# SD.net
KiCad netlist of a schematic drawn in Altium Designer
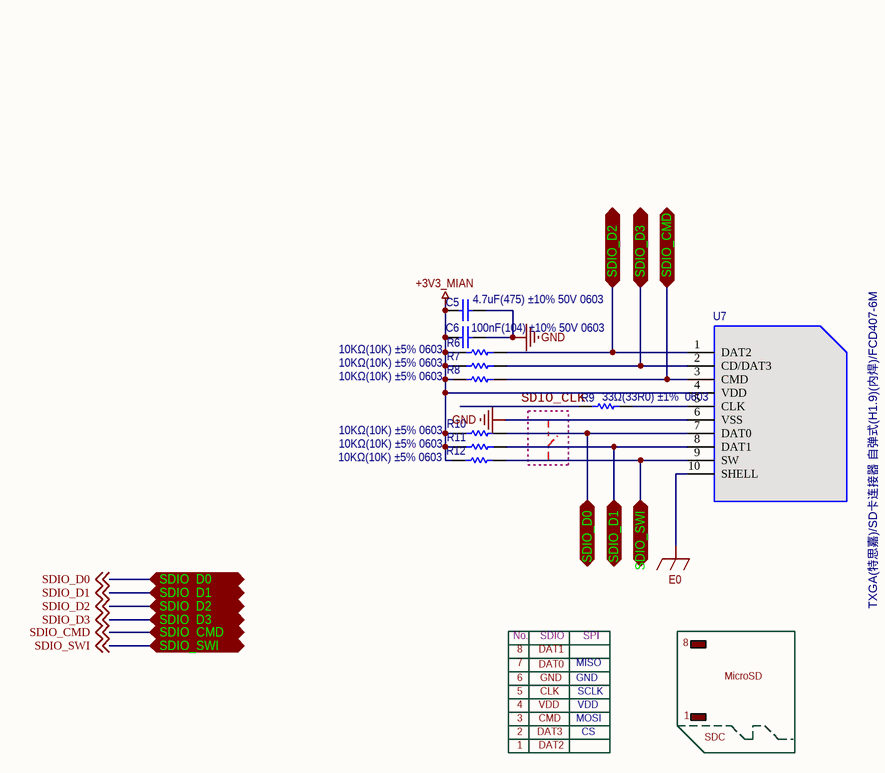
[diagram p0: SD.SchDoc]

(export (version "E")
  (design (tool "Eeschema 10.0.6"))
  (components
    (comp (ref "C5")
      (value "4.7uF(475) ±10% 50V 0603")
      (footprint "C0603")
      (description "Capacitor")
      (fields (field (name "PUBLISHER") "Altium Limited"))
      (libsource (lib "Miscellaneous Devices") (part "Cap"))
    )
    (comp (ref "C6")
      (value "100nF(104) ±10% 50V 0603")
      (footprint "C0603")
      (description "Capacitor")
      (fields (field (name "PUBLISHER") "Altium Limited"))
      (libsource (lib "Miscellaneous Devices") (part "Cap"))
    )
    (comp (ref "R6")
      (value "10KΩ(10K) ±5% 0603")
      (footprint "R0603")
      (description "Resistor")
      (fields (field (name "PUBLISHER") "Altium Limited"))
      (libsource (lib "Miscellaneous Devices") (part "Res1"))
    )
    (comp (ref "R7")
      (value "10KΩ(10K) ±5% 0603")
      (footprint "R0603")
      (description "Resistor")
      (fields (field (name "PUBLISHER") "Altium Limited"))
      (libsource (lib "Miscellaneous Devices") (part "Res1"))
    )
    (comp (ref "R8")
      (value "10KΩ(10K) ±5% 0603")
      (footprint "R0603")
      (description "Resistor")
      (fields (field (name "PUBLISHER") "Altium Limited"))
      (libsource (lib "Miscellaneous Devices") (part "Res1"))
    )
    (comp (ref "R9")
      (value "33Ω(33R0) ±1%  0603")
      (footprint "R0603")
      (description "Resistor")
      (fields (field (name "PUBLISHER") "Altium Limited"))
      (libsource (lib "Miscellaneous Devices") (part "Res1"))
    )
    (comp (ref "R10")
      (value "10KΩ(10K) ±5% 0603")
      (footprint "R0603")
      (description "Resistor")
      (fields (field (name "PUBLISHER") "Altium Limited"))
      (libsource (lib "Miscellaneous Devices") (part "Res1"))
    )
    (comp (ref "R11")
      (value "10KΩ(10K) ±5% 0603")
      (footprint "R0603")
      (description "Resistor")
      (fields (field (name "PUBLISHER") "Altium Limited"))
      (libsource (lib "Miscellaneous Devices") (part "Res1"))
    )
    (comp (ref "R12")
      (value "10KΩ(10K) ±5% 0603")
      (footprint "R0603")
      (description "Resistor")
      (fields (field (name "PUBLISHER") "Altium Limited"))
      (libsource (lib "Miscellaneous Devices") (part "Res1"))
    )
    (comp (ref "U7")
      (value "TXGA(特思嘉)/SD卡连接器 自弹式(H1.9)(内焊)/FCD407-6M")
      (footprint "Micro SD")
      (libsource (lib "Tek") (part "SD CARD/FCD407-6M"))
    )
  )
  (nets
    (net (code "1") (name "+3V3_MIAN") (class "Default")
      (node (ref "C5") (pin "1") (pinfunction "1_1") (pintype "passive"))
      (node (ref "C6") (pin "2") (pinfunction "2_2") (pintype "passive"))
      (node (ref "R10") (pin "2") (pinfunction "2_2") (pintype "passive"))
      (node (ref "R11") (pin "2") (pinfunction "2_2") (pintype "passive"))
      (node (ref "R12") (pin "2") (pinfunction "2_2") (pintype "passive"))
      (node (ref "R6") (pin "2") (pinfunction "2_2") (pintype "passive"))
      (node (ref "R7") (pin "2") (pinfunction "2_2") (pintype "passive"))
      (node (ref "R8") (pin "2") (pinfunction "2_2") (pintype "passive"))
      (node (ref "U7") (pin "4") (pinfunction "VDD_4") (pintype "passive"))
    )
    (net (code "2") (name "/SDIO_CLK") (class "Default")
      (node (ref "R9") (pin "2") (pinfunction "2_2") (pintype "passive"))
    )
    (net (code "3") (name "E0") (class "Default")
      (node (ref "U7") (pin "10") (pinfunction "SHELL_10") (pintype "passive"))
    )
    (net (code "4") (name "GND") (class "Default")
      (node (ref "C5") (pin "2") (pinfunction "2_2") (pintype "passive"))
      (node (ref "C6") (pin "1") (pinfunction "1_1") (pintype "passive"))
      (node (ref "U7") (pin "6") (pinfunction "VSS_6") (pintype "passive"))
    )
    (net (code "5") (name "Net-(U7-CLK)") (class "Default")
      (node (ref "R9") (pin "1") (pinfunction "1_1") (pintype "passive"))
      (node (ref "U7") (pin "5") (pinfunction "CLK_5") (pintype "passive"))
    )
    (net (code "6") (name "SDIO_CMD") (class "Default")
      (node (ref "R8") (pin "1") (pinfunction "1_1") (pintype "passive"))
      (node (ref "U7") (pin "3") (pinfunction "CMD_3") (pintype "passive"))
    )
    (net (code "7") (name "SDIO_D0") (class "Default")
      (node (ref "R10") (pin "1") (pinfunction "1_1") (pintype "passive"))
      (node (ref "U7") (pin "7") (pinfunction "DAT0_7") (pintype "passive"))
    )
    (net (code "8") (name "SDIO_D1") (class "Default")
      (node (ref "R11") (pin "1") (pinfunction "1_1") (pintype "passive"))
      (node (ref "U7") (pin "8") (pinfunction "DAT1_8") (pintype "passive"))
    )
    (net (code "9") (name "SDIO_D2") (class "Default")
      (node (ref "R6") (pin "1") (pinfunction "1_1") (pintype "passive"))
      (node (ref "U7") (pin "1") (pinfunction "DAT2_1") (pintype "passive"))
    )
    (net (code "10") (name "SDIO_D3") (class "Default")
      (node (ref "R7") (pin "1") (pinfunction "1_1") (pintype "passive"))
      (node (ref "U7") (pin "2") (pinfunction "CD/DAT3_2") (pintype "passive"))
    )
    (net (code "11") (name "SDIO_SWI") (class "Default")
      (node (ref "R12") (pin "1") (pinfunction "1_1") (pintype "passive"))
      (node (ref "U7") (pin "9") (pinfunction "SW_9") (pintype "passive"))
    )
  )
)
